# Industrial-Controller_USB.net
KiCad netlist of a schematic drawn in Altium Designer
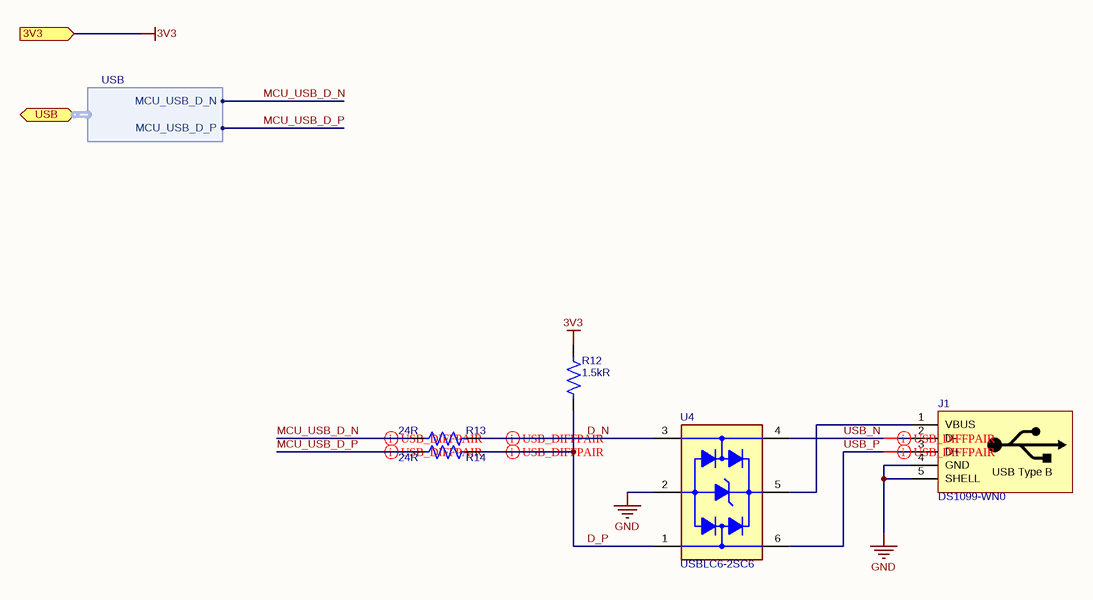
[diagram p0: Industrial-Controller_USB.SchDoc]

(export (version "E")
  (design (tool "Eeschema 10.0.6"))
  (components
    (comp (ref "J1")
      (value "DS1099-WN0")
      (footprint "DS1099-WN0")
      (description "CONN TYPE B SKT HORIZONTAL TH")
      (libsource (lib "Industrial-Controller") (part "DS1099-WN0"))
    )
    (comp (ref "R12")
      (value "1.5kR")
      (footprint "RES_0603")
      (description "RES 1.5K OHM 1% 1/10W 0603")
      (fields (field (name "TOLERANCE") "1%"))
      (libsource (lib "Industrial-Controller") (part "RC0603FR-071K5L"))
    )
    (comp (ref "R13")
      (value "24R")
      (footprint "RES_0603")
      (description "RES 24 OHM 1% 1/10W 0603")
      (fields (field (name "TOLERANCE") "1%"))
      (libsource (lib "Industrial-Controller") (part "RC0603FR-0724RL"))
    )
    (comp (ref "R14")
      (value "24R")
      (footprint "RES_0603")
      (description "RES 24 OHM 1% 1/10W 0603")
      (fields (field (name "TOLERANCE") "1%"))
      (libsource (lib "Industrial-Controller") (part "RC0603FR-0724RL"))
    )
    (comp (ref "U4")
      (value "USBLC6-2SC6")
      (footprint "SOT-23-6")
      (description "TVS DIODE 5.25VWM 17VC SOT23-6")
      (libsource (lib "Industrial-Controller") (part "USBLC6-2SC6"))
    )
  )
  (nets
    (net (code "2") (name "/D_N") (class "Default")
      (node (ref "R13") (pin "2") (pinfunction "2_2") (pintype "passive"))
      (node (ref "U4") (pin "3") (pinfunction "I/O_2_3") (pintype "passive"))
    )
    (net (code "3") (name "/D_P") (class "Default")
      (node (ref "R12") (pin "2") (pinfunction "2_2") (pintype "passive"))
      (node (ref "R14") (pin "2") (pinfunction "2_2") (pintype "passive"))
      (node (ref "U4") (pin "1") (pinfunction "I/O_1_1") (pintype "passive"))
    )
    (net (code "4") (name "/MCU_USB_D_N") (class "Default")
      (node (ref "R13") (pin "1") (pinfunction "1_1") (pintype "passive"))
    )
    (net (code "5") (name "/MCU_USB_D_P") (class "Default")
      (node (ref "R14") (pin "1") (pinfunction "1_1") (pintype "passive"))
    )
    (net (code "6") (name "/USB_N") (class "Default")
      (node (ref "J1") (pin "2") (pinfunction "D-_2") (pintype "passive"))
      (node (ref "U4") (pin "4") (pinfunction "I/O_3_4") (pintype "passive"))
    )
    (net (code "7") (name "/USB_P") (class "Default")
      (node (ref "J1") (pin "3") (pinfunction "D+_3") (pintype "passive"))
      (node (ref "U4") (pin "6") (pinfunction "I/O_4_6") (pintype "passive"))
    )
    (net (code "9") (name "3V3") (class "Default")
      (node (ref "R12") (pin "1") (pinfunction "1_1") (pintype "passive"))
    )
    (net (code "10") (name "GND") (class "Default")
      (node (ref "J1") (pin "4") (pinfunction "GND_4") (pintype "passive"))
      (node (ref "J1") (pin "5") (pinfunction "SHELL_5") (pintype "passive"))
      (node (ref "U4") (pin "2") (pinfunction "GND_2") (pintype "passive"))
    )
    (net (code "11") (name "Net-(J1-VBUS)") (class "Default")
      (node (ref "J1") (pin "1") (pinfunction "VBUS_1") (pintype "passive"))
      (node (ref "U4") (pin "5") (pinfunction "VBUS_5") (pintype "passive"))
    )
  )
)
